# TSOC_ESP32S.net
KiCad netlist of a schematic drawn in EAGLE
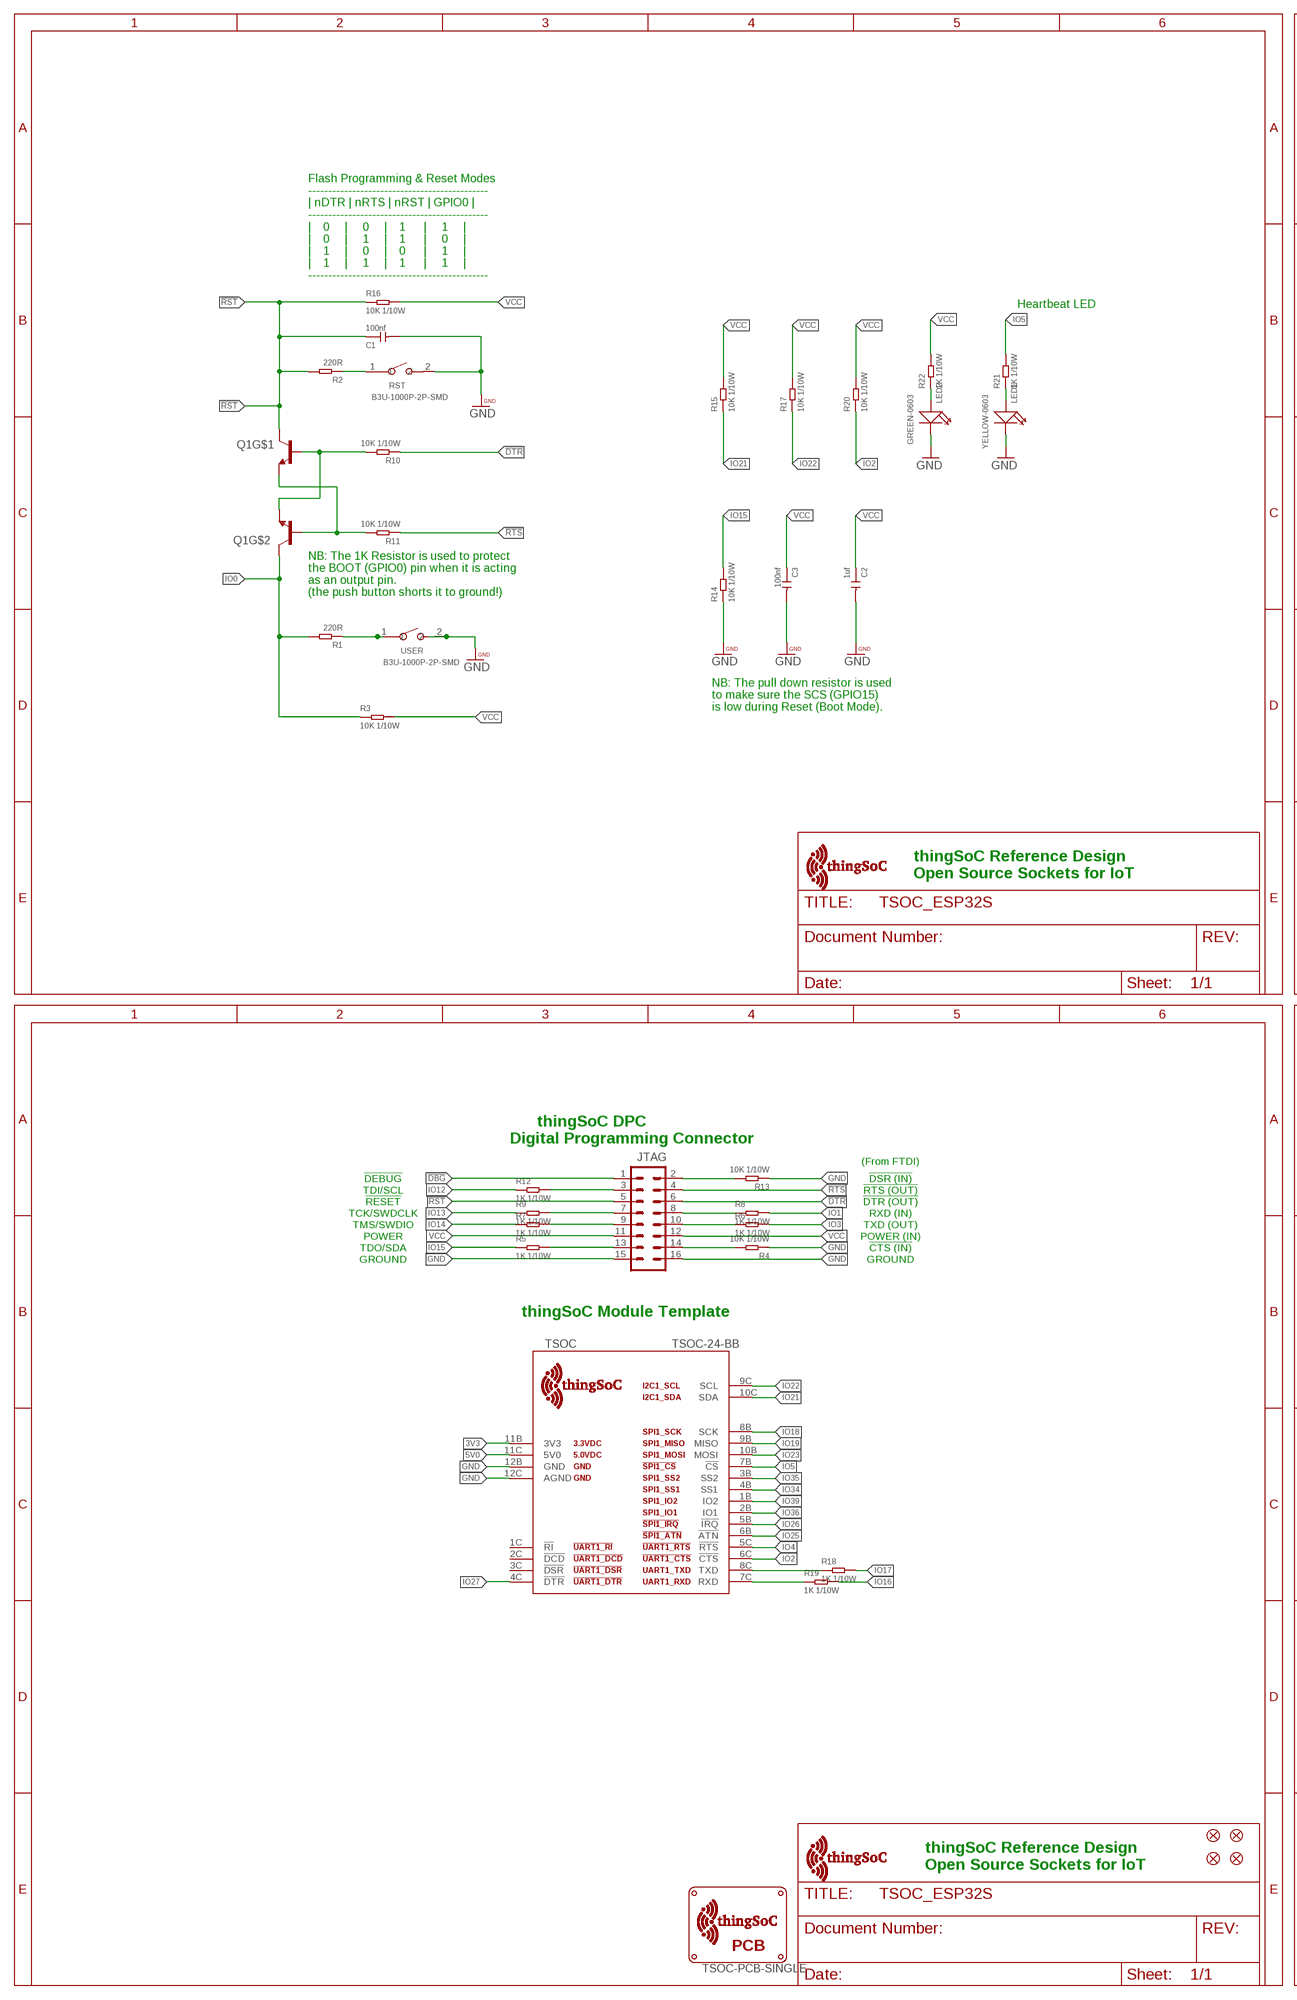
[diagram p0: schematic, sheet 1, part 1 of 2]
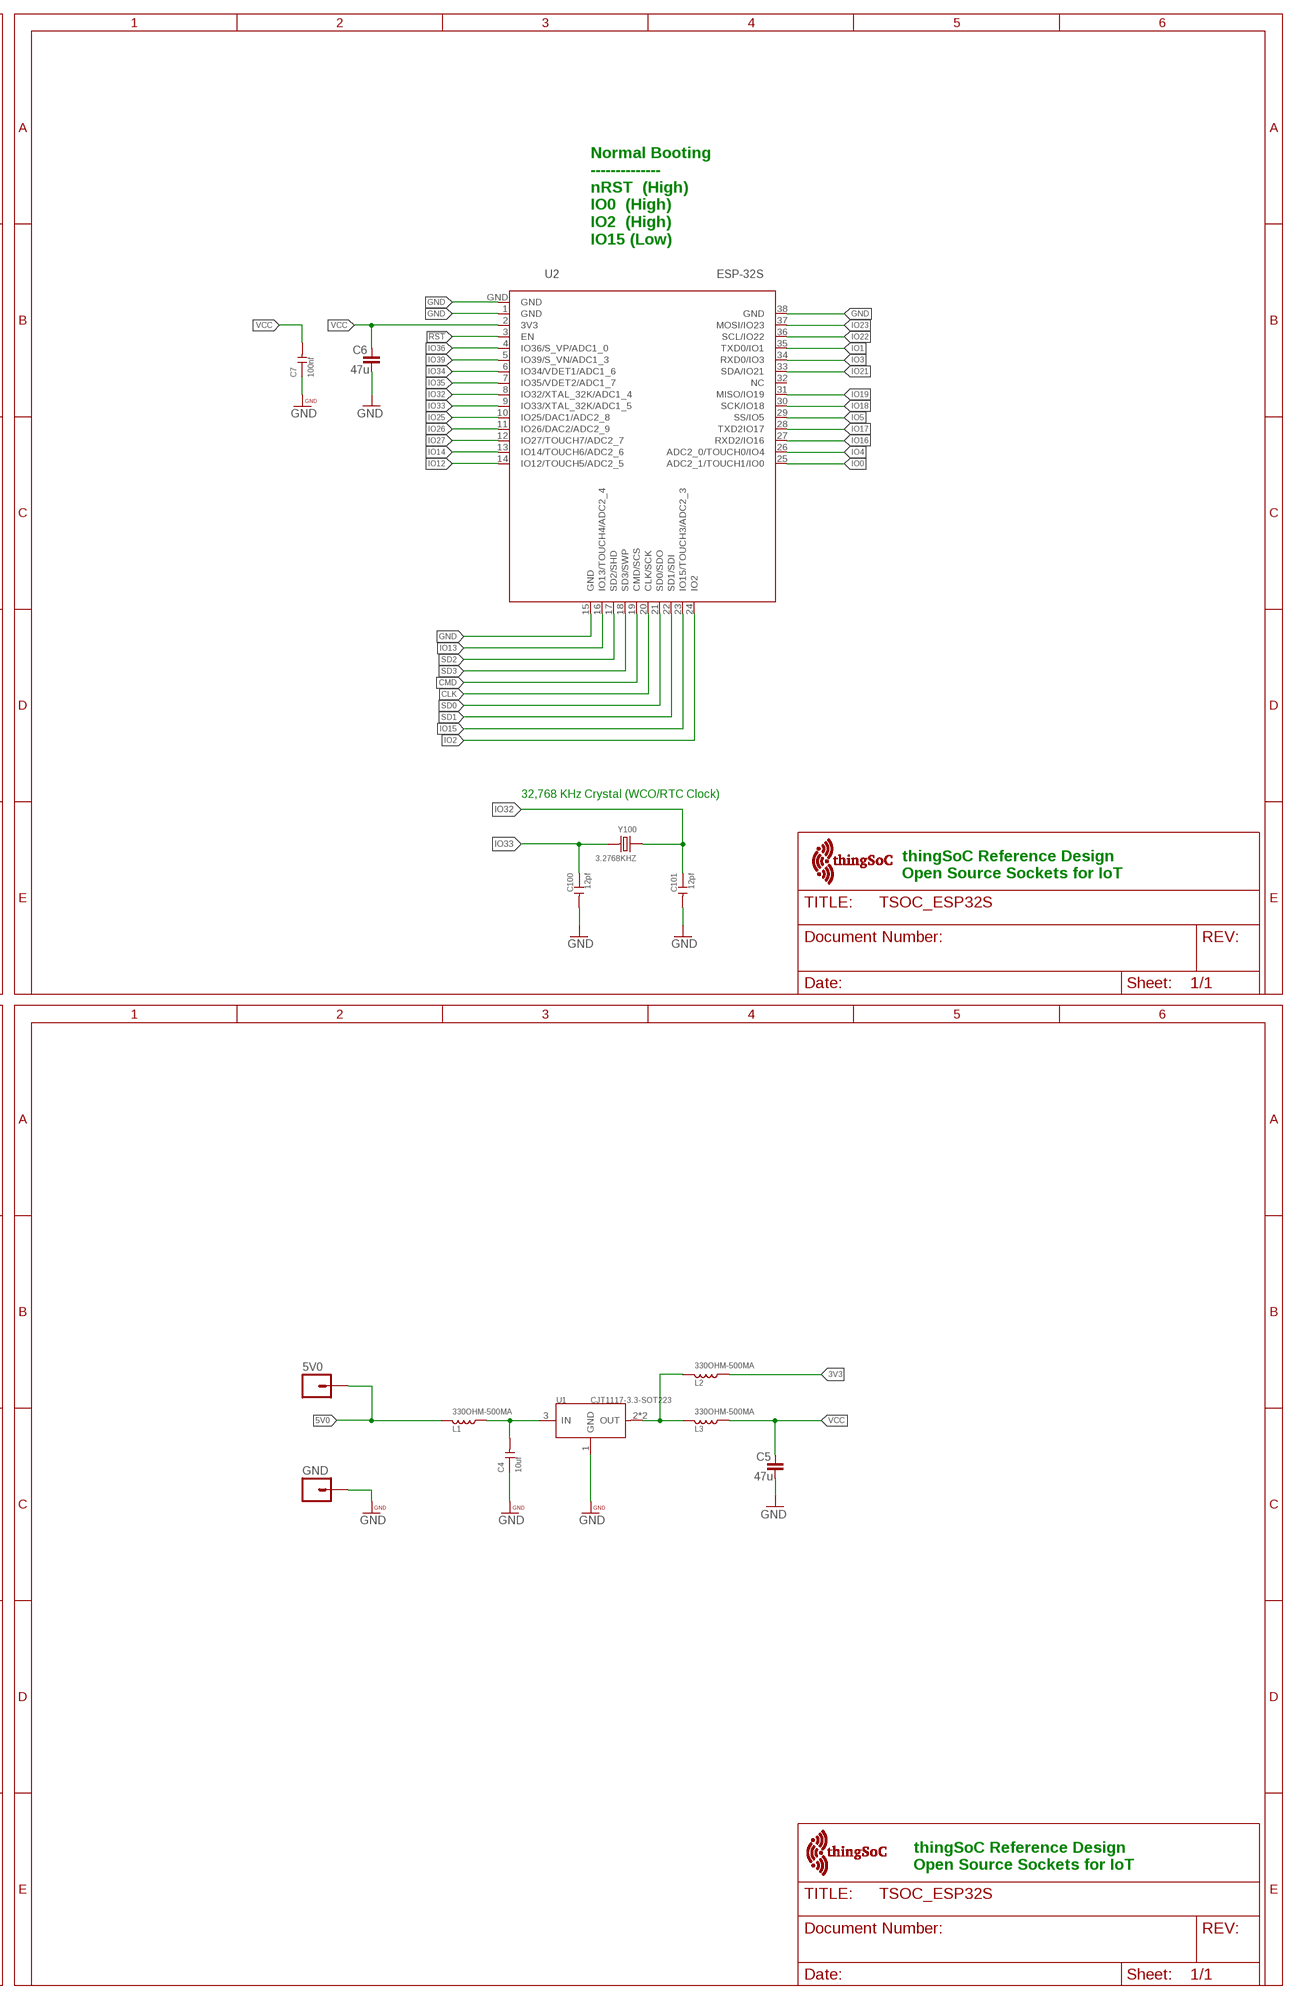
[diagram p1: schematic, sheet 1, part 2 of 2]

(export (version "E")
  (design (tool "Eeschema 10.0.6"))
  (components
    (comp (ref "$$U$1")
      (value "TSOC-LOGO-SMALL")
      (footprint "eagle-import:TSOC-LOGO-SML")
      (libsource (lib "eagle-import") (part "TSOC-LOGO-SMALL"))
    )
    (comp (ref "$$U$2")
      (value "TSOC-LOGO-SMALL")
      (footprint "eagle-import:TSOC-LOGO-SML")
      (libsource (lib "eagle-import") (part "TSOC-LOGO-SMALL"))
    )
    (comp (ref "5V0")
      (value "M01PTH")
      (footprint "eagle-import:1X01")
      (libsource (lib "eagle-import") (part "M01PTH"))
    )
    (comp (ref "BRD")
      (value "TSOC-PCB-SINGLE")
      (footprint "eagle-import:TSOC-BB-BRD-DIM")
      (libsource (lib "eagle-import") (part "TSOC-PCB-SINGLE"))
    )
    (comp (ref "C1")
      (value "100nf")
      (footprint "eagle-import:C0603")
      (fields (field (name "MPN") "CC0603KRX7R9BB104"))
      (libsource (lib "eagle-import") (part "CERAMIC-100NF-50V-10%-X7R(0603)"))
    )
    (comp (ref "C2")
      (value "1uf")
      (footprint "eagle-import:C0603")
      (fields (field (name "MPN") "CC0603KRX7R8BB105"))
      (libsource (lib "eagle-import") (part "CERAMIC-1UF-25V-10%-X7R(0603)"))
    )
    (comp (ref "C3")
      (value "100nf")
      (footprint "eagle-import:C0603")
      (fields (field (name "MPN") "CC0603KRX7R9BB104"))
      (libsource (lib "eagle-import") (part "CERAMIC-100NF-50V-10%-X7R(0603)"))
    )
    (comp (ref "C4")
      (value "10uf")
      (footprint "eagle-import:C0603")
      (fields (field (name "MPN") "CC0603KRX5R6BB106"))
      (libsource (lib "eagle-import") (part "CERAMIC-10UF-10V-10%-X5R(0603)"))
    )
    (comp (ref "C5")
      (value "47u")
      (footprint "eagle-import:C1206")
      (libsource (lib "eagle-import") (part "CAPACITOR-1206"))
    )
    (comp (ref "C6")
      (value "47u")
      (footprint "eagle-import:C1206")
      (libsource (lib "eagle-import") (part "CAPACITOR-1206"))
    )
    (comp (ref "C7")
      (value "100nf")
      (footprint "eagle-import:C0603")
      (fields (field (name "MPN") "CC0603KRX5R6BB106"))
      (libsource (lib "eagle-import") (part "CERAMIC-10UF-10V-10%-X5R(0603)"))
    )
    (comp (ref "C100")
      (value "12pf")
      (footprint "eagle-import:C0603")
      (fields (field (name "MPN") "CC0603JRNPO9BN120"))
      (libsource (lib "eagle-import") (part "CERAMIC-12PF-50V-5%-NPO(0603)"))
    )
    (comp (ref "C101")
      (value "12pf")
      (footprint "eagle-import:C0603")
      (fields (field (name "MPN") "CC0603JRNPO9BN120"))
      (libsource (lib "eagle-import") (part "CERAMIC-12PF-50V-5%-NPO(0603)"))
    )
    (comp (ref "FID1")
      (value "FIDUCIALUFIDUCIAL")
      (footprint "eagle-import:MICRO-FIDUCIAL")
      (libsource (lib "eagle-import") (part "FIDUCIALUFIDUCIAL"))
    )
    (comp (ref "FID2")
      (value "FIDUCIALUFIDUCIAL")
      (footprint "eagle-import:MICRO-FIDUCIAL")
      (libsource (lib "eagle-import") (part "FIDUCIALUFIDUCIAL"))
    )
    (comp (ref "FID3")
      (value "FIDUCIALUFIDUCIAL")
      (footprint "eagle-import:MICRO-FIDUCIAL")
      (libsource (lib "eagle-import") (part "FIDUCIALUFIDUCIAL"))
    )
    (comp (ref "FID4")
      (value "FIDUCIALUFIDUCIAL")
      (footprint "eagle-import:MICRO-FIDUCIAL")
      (libsource (lib "eagle-import") (part "FIDUCIALUFIDUCIAL"))
    )
    (comp (ref "GND")
      (value "M01PTH")
      (footprint "eagle-import:1X01")
      (libsource (lib "eagle-import") (part "M01PTH"))
    )
    (comp (ref "JTAG")
      (value "M08X2")
      (footprint "eagle-import:2X8")
      (libsource (lib "eagle-import") (part "M08X2"))
    )
    (comp (ref "L1")
      (value "330OHM-500MA")
      (footprint "eagle-import:L0603")
      (fields (field (name "MPN") "BLM18AG121SN1D"))
      (libsource (lib "eagle-import") (part "SMD-FERRITE-CHIP-120-OHM-500MA(0603)"))
    )
    (comp (ref "L2")
      (value "330OHM-500MA")
      (footprint "eagle-import:L0603")
      (fields (field (name "MPN") "BLM18AG121SN1D"))
      (libsource (lib "eagle-import") (part "SMD-FERRITE-CHIP-120-OHM-500MA(0603)"))
    )
    (comp (ref "L3")
      (value "330OHM-500MA")
      (footprint "eagle-import:L0603")
      (fields (field (name "MPN") "BLM18AG121SN1D"))
      (libsource (lib "eagle-import") (part "SMD-FERRITE-CHIP-120-OHM-500MA(0603)"))
    )
    (comp (ref "LED1")
      (value "YELLOW-0603")
      (footprint "eagle-import:LED-0603")
      (fields (field (name "MPN") "19-217-Y5C-AM1N1VY-3T"))
      (libsource (lib "eagle-import") (part "SMD-LED-CLEAR-YELLOW(0603)"))
    )
    (comp (ref "LED2")
      (value "GREEN-0603")
      (footprint "eagle-import:LED-0603")
      (fields (field (name "MPN") "19-217-G7C-AN1P2-3T"))
      (libsource (lib "eagle-import") (part "SMD-LED-CLEAR-GREEN(0603)"))
    )
    (comp (ref "Q1")
      (value "MMBT2222A")
      (footprint "eagle-import:SOT363")
      (libsource (lib "eagle-import") (part "MMDT3904"))
    )
    (comp (ref "R1")
      (value "220R")
      (footprint "eagle-import:R0603")
      (fields (field (name "MPN") "RC0603JR-07220RL"))
      (libsource (lib "eagle-import") (part "SMD-RES-220R-5%-1/10W(0603)"))
    )
    (comp (ref "R2")
      (value "220R")
      (footprint "eagle-import:R0603")
      (fields (field (name "MPN") "RC0603JR-07220RL"))
      (libsource (lib "eagle-import") (part "SMD-RES-220R-5%-1/10W(0603)"))
    )
    (comp (ref "R3")
      (value "10K 1/10W")
      (footprint "eagle-import:R0603")
      (fields (field (name "MPN") "RC0603JR-0710KL"))
      (libsource (lib "eagle-import") (part "SMD-RES-10K-5%-1/10W(0603)"))
    )
    (comp (ref "R4")
      (value "10K 1/10W")
      (footprint "eagle-import:R0603")
      (fields (field (name "MPN") "RC0603JR-0710KL"))
      (libsource (lib "eagle-import") (part "SMD-RES-10K-5%-1/10W(0603)"))
    )
    (comp (ref "R5")
      (value "1K 1/10W")
      (footprint "eagle-import:R0603")
      (fields (field (name "MPN") "RC0603JR-071KL"))
      (libsource (lib "eagle-import") (part "SMD-RES-1K-5%-1/10W(0603)"))
    )
    (comp (ref "R6")
      (value "1K 1/10W")
      (footprint "eagle-import:R0603")
      (fields (field (name "MPN") "RC0603JR-071KL"))
      (libsource (lib "eagle-import") (part "SMD-RES-1K-5%-1/10W(0603)"))
    )
    (comp (ref "R7")
      (value "1K 1/10W")
      (footprint "eagle-import:R0603")
      (fields (field (name "MPN") "RC0603JR-071KL"))
      (libsource (lib "eagle-import") (part "SMD-RES-1K-5%-1/10W(0603)"))
    )
    (comp (ref "R8")
      (value "1K 1/10W")
      (footprint "eagle-import:R0603")
      (fields (field (name "MPN") "RC0603JR-071KL"))
      (libsource (lib "eagle-import") (part "SMD-RES-1K-5%-1/10W(0603)"))
    )
    (comp (ref "R9")
      (value "1K 1/10W")
      (footprint "eagle-import:R0603")
      (fields (field (name "MPN") "RC0603JR-071KL"))
      (libsource (lib "eagle-import") (part "SMD-RES-1K-5%-1/10W(0603)"))
    )
    (comp (ref "R10")
      (value "10K 1/10W")
      (footprint "eagle-import:R0603")
      (fields (field (name "MPN") "RC0603JR-0710KL"))
      (libsource (lib "eagle-import") (part "SMD-RES-10K-5%-1/10W(0603)"))
    )
    (comp (ref "R11")
      (value "10K 1/10W")
      (footprint "eagle-import:R0603")
      (fields (field (name "MPN") "RC0603JR-0710KL"))
      (libsource (lib "eagle-import") (part "SMD-RES-10K-5%-1/10W(0603)"))
    )
    (comp (ref "R12")
      (value "1K 1/10W")
      (footprint "eagle-import:R0603")
      (fields (field (name "MPN") "RC0603JR-071KL"))
      (libsource (lib "eagle-import") (part "SMD-RES-1K-5%-1/10W(0603)"))
    )
    (comp (ref "R13")
      (value "10K 1/10W")
      (footprint "eagle-import:R0603")
      (fields (field (name "MPN") "RC0603JR-0710KL"))
      (libsource (lib "eagle-import") (part "SMD-RES-10K-5%-1/10W(0603)"))
    )
    (comp (ref "R14")
      (value "10K 1/10W")
      (footprint "eagle-import:R0603")
      (fields (field (name "MPN") "RC0603JR-0710KL"))
      (libsource (lib "eagle-import") (part "SMD-RES-10K-5%-1/10W(0603)"))
    )
    (comp (ref "R15")
      (value "10K 1/10W")
      (footprint "eagle-import:R0603")
      (fields (field (name "MPN") "RC0603JR-0710KL"))
      (libsource (lib "eagle-import") (part "SMD-RES-10K-5%-1/10W(0603)"))
    )
    (comp (ref "R16")
      (value "10K 1/10W")
      (footprint "eagle-import:R0603")
      (fields (field (name "MPN") "RC0603JR-0710KL"))
      (libsource (lib "eagle-import") (part "SMD-RES-10K-5%-1/10W(0603)"))
    )
    (comp (ref "R17")
      (value "10K 1/10W")
      (footprint "eagle-import:R0603")
      (fields (field (name "MPN") "RC0603JR-0710KL"))
      (libsource (lib "eagle-import") (part "SMD-RES-10K-5%-1/10W(0603)"))
    )
    (comp (ref "R18")
      (value "1K 1/10W")
      (footprint "eagle-import:R0603")
      (fields (field (name "MPN") "RC0603JR-071KL"))
      (libsource (lib "eagle-import") (part "SMD-RES-1K-5%-1/10W(0603)"))
    )
    (comp (ref "R19")
      (value "1K 1/10W")
      (footprint "eagle-import:R0603")
      (fields (field (name "MPN") "RC0603JR-071KL"))
      (libsource (lib "eagle-import") (part "SMD-RES-1K-5%-1/10W(0603)"))
    )
    (comp (ref "R20")
      (value "10K 1/10W")
      (footprint "eagle-import:R0603")
      (fields (field (name "MPN") "RC0603JR-0710KL"))
      (libsource (lib "eagle-import") (part "SMD-RES-10K-5%-1/10W(0603)"))
    )
    (comp (ref "R21")
      (value "1K 1/10W")
      (footprint "eagle-import:R0603")
      (fields (field (name "MPN") "RC0603JR-071KL"))
      (libsource (lib "eagle-import") (part "SMD-RES-1K-5%-1/10W(0603)"))
    )
    (comp (ref "R22")
      (value "1K 1/10W")
      (footprint "eagle-import:R0603")
      (fields (field (name "MPN") "RC0603JR-071KL"))
      (libsource (lib "eagle-import") (part "SMD-RES-1K-5%-1/10W(0603)"))
    )
    (comp (ref "RST")
      (value "B3U-1000P-2P-SMD")
      (footprint "eagle-import:SW2-2.6-3.0X2.5X1.2+0.4MM")
      (libsource (lib "eagle-import") (part "SMD-BUTTON(2P-3.0X2.5X1.2+0.4MM)-B3U-1000P-2P-SMD"))
    )
    (comp (ref "TSOC")
      (value "TSOC-24-BB")
      (footprint "eagle-import:TSOC-BB-S24")
      (libsource (lib "eagle-import") (part "TSOC-24-BB"))
    )
    (comp (ref "U$101")
      (value "TSOC-LOGO-SMALL")
      (footprint "eagle-import:TSOC-LOGO-SML")
      (libsource (lib "eagle-import") (part "TSOC-LOGO-SMALL"))
    )
    (comp (ref "U$102")
      (value "TSOC-LOGO-LRG")
      (footprint "eagle-import:TSOC-LOGO-LRG")
      (libsource (lib "eagle-import") (part "TSOC-LOGO-LRG"))
    )
    (comp (ref "U1")
      (value "CJT1117-3.3-SOT223")
      (footprint "eagle-import:SOT-223")
      (fields (field (name "MPN") "CJT1117-3.3"))
      (libsource (lib "eagle-import") (part "PMIC-CJT1117-3.3(SOT223)"))
    )
    (comp (ref "U2")
      (value "ESP-32S")
      (footprint "eagle-import:ESP-32S")
      (libsource (lib "eagle-import") (part "ESP-32S"))
    )
    (comp (ref "USER")
      (value "B3U-1000P-2P-SMD")
      (footprint "eagle-import:SW2-2.6-3.0X2.5X1.2+0.4MM")
      (libsource (lib "eagle-import") (part "SMD-BUTTON(2P-3.0X2.5X1.2+0.4MM)-B3U-1000P-2P-SMD"))
    )
    (comp (ref "Y100")
      (value "3.2768KHZ")
      (footprint "eagle-import:X2-SMD-L2.0X1.2X0.55MM")
      (fields (field (name "MPN") "FC-12M"))
      (libsource (lib "eagle-import") (part "SMD-CRYSTAL-32.768KHZ-12.5PF-20PPM-90K(2P-L2.0X1.2MM)"))
    )
  )
  (nets
    (net (code "1") (name "/~{DBG}") (class "Default")
      (node (ref "JTAG") (pin "1") (pinfunction "1_1") (pintype "passive"))
    )
    (net (code "2") (name "/~{DTR}") (class "Default")
      (node (ref "JTAG") (pin "6") (pinfunction "6_6") (pintype "passive"))
      (node (ref "R10") (pin "1") (pinfunction "1_1") (pintype "passive"))
    )
    (net (code "3") (name "/~{RST}") (class "Default")
      (node (ref "C1") (pin "1") (pinfunction "1_1") (pintype "passive"))
      (node (ref "JTAG") (pin "5") (pinfunction "5_5") (pintype "passive"))
      (node (ref "Q1") (pin "3") (pinfunction "C_3") (pintype "passive"))
      (node (ref "R16") (pin "1") (pinfunction "1_1") (pintype "passive"))
      (node (ref "R2") (pin "2") (pinfunction "2_2") (pintype "passive"))
      (node (ref "U2") (pin "3") (pinfunction "EN_3") (pintype "bidirectional"))
    )
    (net (code "4") (name "/~{RTS}") (class "Default")
      (node (ref "JTAG") (pin "4") (pinfunction "4_4") (pintype "passive"))
      (node (ref "R11") (pin "1") (pinfunction "1_1") (pintype "passive"))
    )
    (net (code "5") (name "3V3") (class "Default")
      (node (ref "L2") (pin "2") (pinfunction "2_2") (pintype "passive"))
      (node (ref "TSOC") (pin "11B") (pinfunction "3V3_11B") (pintype "bidirectional"))
    )
    (net (code "6") (name "5V0") (class "Default")
      (node (ref "5V0") (pin "1") (pinfunction "1_1") (pintype "passive"))
      (node (ref "L1") (pin "1") (pinfunction "1_1") (pintype "passive"))
      (node (ref "TSOC") (pin "11C") (pinfunction "5V0_11C") (pintype "bidirectional"))
    )
    (net (code "7") (name "CLK") (class "Default")
      (node (ref "U2") (pin "20") (pinfunction "CLK/SCK_20") (pintype "bidirectional"))
    )
    (net (code "8") (name "CMD") (class "Default")
      (node (ref "U2") (pin "19") (pinfunction "CMD/SCS_19") (pintype "bidirectional"))
    )
    (net (code "9") (name "GND") (class "Default")
      (node (ref "C1") (pin "2") (pinfunction "2_2") (pintype "passive"))
      (node (ref "C100") (pin "2") (pinfunction "2_2") (pintype "passive"))
      (node (ref "C101") (pin "2") (pinfunction "2_2") (pintype "passive"))
      (node (ref "C2") (pin "2") (pinfunction "2_2") (pintype "passive"))
      (node (ref "C3") (pin "2") (pinfunction "2_2") (pintype "passive"))
      (node (ref "C4") (pin "1") (pinfunction "1_1") (pintype "passive"))
      (node (ref "C5") (pin "1") (pinfunction "1_1") (pintype "passive"))
      (node (ref "C6") (pin "1") (pinfunction "1_1") (pintype "passive"))
      (node (ref "C7") (pin "1") (pinfunction "1_1") (pintype "passive"))
      (node (ref "GND") (pin "1") (pinfunction "1_1") (pintype "passive"))
      (node (ref "JTAG") (pin "15") (pinfunction "15_15") (pintype "passive"))
      (node (ref "JTAG") (pin "16") (pinfunction "16_16") (pintype "passive"))
      (node (ref "LED1") (pin "-") (pinfunction "-_-") (pintype "passive"))
      (node (ref "LED2") (pin "-") (pinfunction "-_-") (pintype "passive"))
      (node (ref "R13") (pin "1") (pinfunction "1_1") (pintype "passive"))
      (node (ref "R14") (pin "1") (pinfunction "1_1") (pintype "passive"))
      (node (ref "R4") (pin "1") (pinfunction "1_1") (pintype "passive"))
      (node (ref "RST") (pin "2") (pinfunction "2_2") (pintype "bidirectional"))
      (node (ref "TSOC") (pin "12B") (pinfunction "GND_12B") (pintype "bidirectional"))
      (node (ref "TSOC") (pin "12C") (pinfunction "AGND_12C") (pintype "bidirectional"))
      (node (ref "U1") (pin "1") (pinfunction "GND_1") (pintype "bidirectional"))
      (node (ref "U2") (pin "1") (pinfunction "GND_1") (pintype "bidirectional"))
      (node (ref "U2") (pin "15") (pinfunction "GND_15") (pintype "bidirectional"))
      (node (ref "U2") (pin "38") (pinfunction "GND_38") (pintype "bidirectional"))
      (node (ref "U2") (pin "GND") (pinfunction "GND_GND") (pintype "bidirectional"))
      (node (ref "USER") (pin "2") (pinfunction "2_2") (pintype "bidirectional"))
    )
    (net (code "10") (name "IO0") (class "Default")
      (node (ref "Q1") (pin "6") (pinfunction "C_6") (pintype "passive"))
      (node (ref "R1") (pin "2") (pinfunction "2_2") (pintype "passive"))
      (node (ref "R3") (pin "1") (pinfunction "1_1") (pintype "passive"))
      (node (ref "U2") (pin "25") (pinfunction "ADC2_1/TOUCH1/IO0_25") (pintype "bidirectional"))
    )
    (net (code "11") (name "IO1") (class "Default")
      (node (ref "R8") (pin "2") (pinfunction "2_2") (pintype "passive"))
      (node (ref "U2") (pin "35") (pinfunction "TXD0/IO1_35") (pintype "bidirectional"))
    )
    (net (code "12") (name "IO2") (class "Default")
      (node (ref "R20") (pin "1") (pinfunction "1_1") (pintype "passive"))
      (node (ref "TSOC") (pin "6C") (pinfunction "~{CTS}_6C") (pintype "bidirectional"))
      (node (ref "U2") (pin "24") (pinfunction "IO2_24") (pintype "bidirectional"))
    )
    (net (code "13") (name "IO3") (class "Default")
      (node (ref "R6") (pin "2") (pinfunction "2_2") (pintype "passive"))
      (node (ref "U2") (pin "34") (pinfunction "RXD0/IO3_34") (pintype "bidirectional"))
    )
    (net (code "14") (name "IO4") (class "Default")
      (node (ref "TSOC") (pin "5C") (pinfunction "~{RTS}_5C") (pintype "bidirectional"))
      (node (ref "U2") (pin "26") (pinfunction "ADC2_0/TOUCH0/IO4_26") (pintype "bidirectional"))
    )
    (net (code "15") (name "IO5") (class "Default")
      (node (ref "R21") (pin "2") (pinfunction "2_2") (pintype "passive"))
      (node (ref "TSOC") (pin "7B") (pinfunction "~{CS}_7B") (pintype "bidirectional"))
      (node (ref "U2") (pin "29") (pinfunction "SS/IO5_29") (pintype "bidirectional"))
    )
    (net (code "16") (name "IO12") (class "Default")
      (node (ref "R12") (pin "1") (pinfunction "1_1") (pintype "passive"))
      (node (ref "U2") (pin "14") (pinfunction "IO12/TOUCH5/ADC2_5_14") (pintype "bidirectional"))
    )
    (net (code "17") (name "IO13") (class "Default")
      (node (ref "R9") (pin "1") (pinfunction "1_1") (pintype "passive"))
      (node (ref "U2") (pin "16") (pinfunction "IO13/TOUCH4/ADC2_4_16") (pintype "bidirectional"))
    )
    (net (code "18") (name "IO14") (class "Default")
      (node (ref "R7") (pin "1") (pinfunction "1_1") (pintype "passive"))
      (node (ref "U2") (pin "13") (pinfunction "IO14/TOUCH6/ADC2_6_13") (pintype "bidirectional"))
    )
    (net (code "19") (name "IO15") (class "Default")
      (node (ref "R14") (pin "2") (pinfunction "2_2") (pintype "passive"))
      (node (ref "R5") (pin "1") (pinfunction "1_1") (pintype "passive"))
      (node (ref "U2") (pin "23") (pinfunction "IO15/TOUCH3/ADC2_3_23") (pintype "bidirectional"))
    )
    (net (code "20") (name "IO16") (class "Default")
      (node (ref "R19") (pin "2") (pinfunction "2_2") (pintype "passive"))
      (node (ref "U2") (pin "27") (pinfunction "RXD2/IO16_27") (pintype "bidirectional"))
    )
    (net (code "21") (name "IO17") (class "Default")
      (node (ref "R18") (pin "2") (pinfunction "2_2") (pintype "passive"))
      (node (ref "U2") (pin "28") (pinfunction "TXD2IO17_28") (pintype "bidirectional"))
    )
    (net (code "22") (name "IO18") (class "Default")
      (node (ref "TSOC") (pin "8B") (pinfunction "SCK_8B") (pintype "bidirectional"))
      (node (ref "U2") (pin "30") (pinfunction "SCK/IO18_30") (pintype "bidirectional"))
    )
    (net (code "23") (name "IO19") (class "Default")
      (node (ref "TSOC") (pin "9B") (pinfunction "MISO_9B") (pintype "bidirectional"))
      (node (ref "U2") (pin "31") (pinfunction "MISO/IO19_31") (pintype "bidirectional"))
    )
    (net (code "24") (name "IO21") (class "Default")
      (node (ref "R15") (pin "1") (pinfunction "1_1") (pintype "passive"))
      (node (ref "TSOC") (pin "10C") (pinfunction "SDA_10C") (pintype "bidirectional"))
      (node (ref "U2") (pin "33") (pinfunction "SDA/IO21_33") (pintype "bidirectional"))
    )
    (net (code "25") (name "IO22") (class "Default")
      (node (ref "R17") (pin "1") (pinfunction "1_1") (pintype "passive"))
      (node (ref "TSOC") (pin "9C") (pinfunction "SCL_9C") (pintype "bidirectional"))
      (node (ref "U2") (pin "36") (pinfunction "SCL/IO22_36") (pintype "bidirectional"))
    )
    (net (code "26") (name "IO23") (class "Default")
      (node (ref "TSOC") (pin "10B") (pinfunction "MOSI_10B") (pintype "bidirectional"))
      (node (ref "U2") (pin "37") (pinfunction "MOSI/IO23_37") (pintype "bidirectional"))
    )
    (net (code "27") (name "IO25") (class "Default")
      (node (ref "TSOC") (pin "6B") (pinfunction "~{ATN}_6B") (pintype "bidirectional"))
      (node (ref "U2") (pin "10") (pinfunction "IO25/DAC1/ADC2_8_10") (pintype "bidirectional"))
    )
    (net (code "28") (name "IO26") (class "Default")
      (node (ref "TSOC") (pin "5B") (pinfunction "~{IRQ}_5B") (pintype "bidirectional"))
      (node (ref "U2") (pin "11") (pinfunction "IO26/DAC2/ADC2_9_11") (pintype "bidirectional"))
    )
    (net (code "29") (name "IO27") (class "Default")
      (node (ref "TSOC") (pin "4C") (pinfunction "~{DTR}_4C") (pintype "bidirectional"))
      (node (ref "U2") (pin "12") (pinfunction "IO27/TOUCH7/ADC2_7_12") (pintype "bidirectional"))
    )
    (net (code "30") (name "IO32") (class "Default")
      (node (ref "C101") (pin "1") (pinfunction "1_1") (pintype "passive"))
      (node (ref "U2") (pin "8") (pinfunction "IO32/XTAL_32K/ADC1_4_8") (pintype "bidirectional"))
      (node (ref "Y100") (pin "1") (pinfunction "1_1") (pintype "passive"))
    )
    (net (code "31") (name "IO33") (class "Default")
      (node (ref "C100") (pin "1") (pinfunction "1_1") (pintype "passive"))
      (node (ref "U2") (pin "9") (pinfunction "IO33/XTAL_32K/ADC1_5_9") (pintype "bidirectional"))
      (node (ref "Y100") (pin "2") (pinfunction "2_2") (pintype "passive"))
    )
    (net (code "32") (name "IO34") (class "Default")
      (node (ref "TSOC") (pin "4B") (pinfunction "SS1_4B") (pintype "bidirectional"))
      (node (ref "U2") (pin "6") (pinfunction "IO34/VDET1/ADC1_6_6") (pintype "bidirectional"))
    )
    (net (code "33") (name "IO35") (class "Default")
      (node (ref "TSOC") (pin "3B") (pinfunction "SS2_3B") (pintype "bidirectional"))
      (node (ref "U2") (pin "7") (pinfunction "IO35/VDET2/ADC1_7_7") (pintype "bidirectional"))
    )
    (net (code "34") (name "IO36") (class "Default")
      (node (ref "TSOC") (pin "2B") (pinfunction "IO1_2B") (pintype "bidirectional"))
      (node (ref "U2") (pin "4") (pinfunction "IO36/S_VP/ADC1_0_4") (pintype "bidirectional"))
    )
    (net (code "35") (name "IO39") (class "Default")
      (node (ref "TSOC") (pin "1B") (pinfunction "IO2_1B") (pintype "bidirectional"))
      (node (ref "U2") (pin "5") (pinfunction "IO39/S_VN/ADC1_3_5") (pintype "bidirectional"))
    )
    (net (code "36") (name "Net-(JTAG-Pad2)") (class "Default")
      (node (ref "JTAG") (pin "2") (pinfunction "2_2") (pintype "passive"))
      (node (ref "R13") (pin "2") (pinfunction "2_2") (pintype "passive"))
    )
    (net (code "37") (name "Net-(JTAG-Pad3)") (class "Default")
      (node (ref "JTAG") (pin "3") (pinfunction "3_3") (pintype "passive"))
      (node (ref "R12") (pin "2") (pinfunction "2_2") (pintype "passive"))
    )
    (net (code "38") (name "Net-(JTAG-Pad7)") (class "Default")
      (node (ref "JTAG") (pin "7") (pinfunction "7_7") (pintype "passive"))
      (node (ref "R9") (pin "2") (pinfunction "2_2") (pintype "passive"))
    )
    (net (code "39") (name "Net-(JTAG-Pad8)") (class "Default")
      (node (ref "JTAG") (pin "8") (pinfunction "8_8") (pintype "passive"))
      (node (ref "R8") (pin "1") (pinfunction "1_1") (pintype "passive"))
    )
    (net (code "40") (name "Net-(JTAG-Pad9)") (class "Default")
      (node (ref "JTAG") (pin "9") (pinfunction "9_9") (pintype "passive"))
      (node (ref "R7") (pin "2") (pinfunction "2_2") (pintype "passive"))
    )
    (net (code "41") (name "Net-(JTAG-Pad10)") (class "Default")
      (node (ref "JTAG") (pin "10") (pinfunction "10_10") (pintype "passive"))
      (node (ref "R6") (pin "1") (pinfunction "1_1") (pintype "passive"))
    )
    (net (code "42") (name "Net-(JTAG-Pad13)") (class "Default")
      (node (ref "JTAG") (pin "13") (pinfunction "13_13") (pintype "passive"))
      (node (ref "R5") (pin "2") (pinfunction "2_2") (pintype "passive"))
    )
    (net (code "43") (name "Net-(JTAG-Pad14)") (class "Default")
      (node (ref "JTAG") (pin "14") (pinfunction "14_14") (pintype "passive"))
      (node (ref "R4") (pin "2") (pinfunction "2_2") (pintype "passive"))
    )
    (net (code "44") (name "Net-(L2-Pad1)") (class "Default")
      (node (ref "L2") (pin "1") (pinfunction "1_1") (pintype "passive"))
      (node (ref "L3") (pin "1") (pinfunction "1_1") (pintype "passive"))
      (node (ref "U1") (pin "2") (pinfunction "OUT_2") (pintype "bidirectional"))
      (node (ref "U1") (pin "TER") (pinfunction "OUT_TER") (pintype "bidirectional"))
    )
    (net (code "45") (name "Net-(LED1-Pad+)") (class "Default")
      (node (ref "LED1") (pin "+") (pinfunction "+_+") (pintype "passive"))
      (node (ref "R21") (pin "1") (pinfunction "1_1") (pintype "passive"))
    )
    (net (code "46") (name "Net-(LED2-Pad+)") (class "Default")
      (node (ref "LED2") (pin "+") (pinfunction "+_+") (pintype "passive"))
      (node (ref "R22") (pin "1") (pinfunction "1_1") (pintype "passive"))
    )
    (net (code "47") (name "Net-(Q1A-B)") (class "Default")
      (node (ref "Q1") (pin "1") (pinfunction "E_1") (pintype "passive"))
      (node (ref "Q1") (pin "5") (pinfunction "B_5") (pintype "passive"))
      (node (ref "R10") (pin "2") (pinfunction "2_2") (pintype "passive"))
    )
    (net (code "48") (name "Net-(Q1A-E)") (class "Default")
      (node (ref "Q1") (pin "2") (pinfunction "B_2") (pintype "passive"))
      (node (ref "Q1") (pin "4") (pinfunction "E_4") (pintype "passive"))
      (node (ref "R11") (pin "2") (pinfunction "2_2") (pintype "passive"))
    )
    (net (code "49") (name "Net-(R1-Pad1)") (class "Default")
      (node (ref "R1") (pin "1") (pinfunction "1_1") (pintype "passive"))
      (node (ref "USER") (pin "1") (pinfunction "1_1") (pintype "bidirectional"))
    )
    (net (code "50") (name "Net-(R2-Pad1)") (class "Default")
      (node (ref "R2") (pin "1") (pinfunction "1_1") (pintype "passive"))
      (node (ref "RST") (pin "1") (pinfunction "1_1") (pintype "bidirectional"))
    )
    (net (code "51") (name "Net-(TSOC-RXD)") (class "Default")
      (node (ref "R19") (pin "1") (pinfunction "1_1") (pintype "passive"))
      (node (ref "TSOC") (pin "7C") (pinfunction "RXD_7C") (pintype "bidirectional"))
    )
    (net (code "52") (name "Net-(TSOC-TXD)") (class "Default")
      (node (ref "R18") (pin "1") (pinfunction "1_1") (pintype "passive"))
      (node (ref "TSOC") (pin "8C") (pinfunction "TXD_8C") (pintype "bidirectional"))
    )
    (net (code "53") (name "Net-(U1-IN)") (class "Default")
      (node (ref "C4") (pin "2") (pinfunction "2_2") (pintype "passive"))
      (node (ref "L1") (pin "2") (pinfunction "2_2") (pintype "passive"))
      (node (ref "U1") (pin "3") (pinfunction "IN_3") (pintype "bidirectional"))
    )
    (net (code "54") (name "SD0") (class "Default")
      (node (ref "U2") (pin "21") (pinfunction "SD0/SDO_21") (pintype "bidirectional"))
    )
    (net (code "55") (name "SD1") (class "Default")
      (node (ref "U2") (pin "22") (pinfunction "SD1/SDI_22") (pintype "bidirectional"))
    )
    (net (code "56") (name "SD2") (class "Default")
      (node (ref "U2") (pin "17") (pinfunction "SD2/SHD_17") (pintype "bidirectional"))
    )
    (net (code "57") (name "SD3") (class "Default")
      (node (ref "U2") (pin "18") (pinfunction "SD3/SWP_18") (pintype "bidirectional"))
    )
    (net (code "58") (name "VCC") (class "Default")
      (node (ref "C2") (pin "1") (pinfunction "1_1") (pintype "passive"))
      (node (ref "C3") (pin "1") (pinfunction "1_1") (pintype "passive"))
      (node (ref "C5") (pin "2") (pinfunction "2_2") (pintype "passive"))
      (node (ref "C6") (pin "2") (pinfunction "2_2") (pintype "passive"))
      (node (ref "C7") (pin "2") (pinfunction "2_2") (pintype "passive"))
      (node (ref "JTAG") (pin "11") (pinfunction "11_11") (pintype "passive"))
      (node (ref "JTAG") (pin "12") (pinfunction "12_12") (pintype "passive"))
      (node (ref "L3") (pin "2") (pinfunction "2_2") (pintype "passive"))
      (node (ref "R15") (pin "2") (pinfunction "2_2") (pintype "passive"))
      (node (ref "R16") (pin "2") (pinfunction "2_2") (pintype "passive"))
      (node (ref "R17") (pin "2") (pinfunction "2_2") (pintype "passive"))
      (node (ref "R20") (pin "2") (pinfunction "2_2") (pintype "passive"))
      (node (ref "R22") (pin "2") (pinfunction "2_2") (pintype "passive"))
      (node (ref "R3") (pin "2") (pinfunction "2_2") (pintype "passive"))
      (node (ref "U2") (pin "2") (pinfunction "3V3_2") (pintype "bidirectional"))
    )
    (net (code "59") (name "unconnected-(TSOC-~{DCD}-Pad2C)") (class "Default")
      (node (ref "TSOC") (pin "2C") (pinfunction "~{DCD}_2C") (pintype "bidirectional"))
    )
    (net (code "60") (name "unconnected-(TSOC-~{DSR}-Pad3C)") (class "Default")
      (node (ref "TSOC") (pin "3C") (pinfunction "~{DSR}_3C") (pintype "bidirectional"))
    )
    (net (code "61") (name "unconnected-(TSOC-~{RI}-Pad1C)") (class "Default")
      (node (ref "TSOC") (pin "1C") (pinfunction "~{RI}_1C") (pintype "bidirectional"))
    )
    (net (code "62") (name "unconnected-(U2-NC-Pad32)") (class "Default")
      (node (ref "U2") (pin "32") (pinfunction "NC_32") (pintype "bidirectional"))
    )
  )
)
